# lm7805-power-supply.net
KiCad netlist of a schematic drawn in Altium Designer
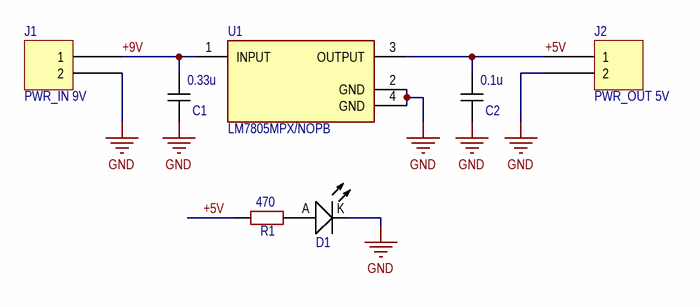
[diagram p0: lm7805-power-supply.SchDoc]

(export (version "E")
  (design (tool "Eeschema 10.0.6"))
  (components
    (comp (ref "C1")
      (value "0.33u")
      (footprint "CAP_CER_1206")
      (description "Cap Cer MLCC SMD 50V 0.33uF X7R 1206 5%")
      (fields
        (field (name "PART NUMBER") "CC1206JRX7R9BB334")
        (field (name "MOUSER PART NUMBER") "603-CC1206JR9BB334")
      )
      (libsource (lib "SssAccesDatbase") (part "Cap"))
    )
    (comp (ref "C2")
      (value "0.1u")
      (footprint "CAP_CER_1206")
      (description "Cap Cer MLCC SMD 50V 0.1uF C0G NP0 1206 5%")
      (fields
        (field (name "PART NUMBER") "C3216C0G1H104J160AA")
        (field (name "MOUSER PART NUMBER") "810-C3216C0G1H104J")
      )
      (libsource (lib "SssAccesDatbase") (part "Cap"))
    )
    (comp (ref "D1")
      (value "Bl 0603")
      (footprint "LED-0603-BLUE")
      (description "LED BLUE DIFFUSED 0603 SMD")
      (fields
        (field (name "PART NUMBER") "150060BS55040")
        (field (name "DIGI-KEY PART NUMBER") "732-12013-1-ND")
      )
      (libsource (lib "SssAccesDatbase") (part "LED_AK"))
    )
    (comp (ref "J1")
      (value "PWR_IN 9V")
      (footprint "TE 282837-2")
      (description "TERM BLK 2P SIDE ENT 5.08MM PCB")
      (fields
        (field (name "PART NUMBER") "282837-2")
        (field (name "MANUFACTURER") "TE Connectivity AMP Connectors")
      )
      (libsource (lib "") (part "2 Pin_1"))
    )
    (comp (ref "J2")
      (value "PWR_OUT 5V")
      (footprint "TE 282837-2")
      (description "TERM BLK 2P SIDE ENT 5.08MM PCB")
      (fields
        (field (name "PART NUMBER") "282837-2")
        (field (name "MANUFACTURER") "TE Connectivity AMP Connectors")
      )
      (libsource (lib "Celestial Altium Library - altium_library") (part "2 Pin"))
    )
    (comp (ref "R1")
      (value "470")
      (footprint "RESC1608(0603)N")
      (description "RES SMD 0603 470  0.5% 25ppm")
      (fields
        (field (name "PART NUMBER") "RN731JTTD4700D25")
        (field (name "MOUSER PART NUMBER") "660-RN731JTTD4700D25")
      )
      (libsource (lib "SssAccesDatbase") (part "Resistor general"))
    )
    (comp (ref "U1")
      (value "LM7805MPX/NOPB")
      (footprint "FP-LM7805MPX-NOPB-MFG")
      (description "IC REG LINEAR 5V 1.5A SOT223-4")
      (fields
        (field (name "MANUFACTURER") "Texas Instruments")
        (field (name "OCTOPART") "https://octopart.com/lm7805mpx%2Fnopb-texas+instruments-74629992")
      )
      (libsource (lib "Altium Content Vault") (part "b4ee7691a89d8e73302b24c49f391f2"))
    )
  )
  (nets
    (net (code "1") (name "/+5V") (class "Default")
      (node (ref "C2") (pin "2") (pinfunction "2_2") (pintype "passive"))
      (node (ref "J2") (pin "1") (pinfunction "1_1") (pintype "passive"))
      (node (ref "R1") (pin "1") (pinfunction "1_1") (pintype "passive"))
      (node (ref "U1") (pin "3") (pinfunction "OUTPUT_3") (pintype "passive"))
    )
    (net (code "2") (name "/+9V") (class "Default")
      (node (ref "C1") (pin "2") (pinfunction "2_2") (pintype "passive"))
      (node (ref "J1") (pin "1") (pinfunction "1_1") (pintype "passive"))
      (node (ref "U1") (pin "1") (pinfunction "INPUT_1") (pintype "power_in"))
    )
    (net (code "3") (name "GND") (class "Default")
      (node (ref "C1") (pin "1") (pinfunction "1_1") (pintype "passive"))
      (node (ref "C2") (pin "1") (pinfunction "1_1") (pintype "passive"))
      (node (ref "D1") (pin "K") (pinfunction "K_K") (pintype "passive"))
      (node (ref "J1") (pin "2") (pinfunction "2_2") (pintype "passive"))
      (node (ref "J2") (pin "2") (pinfunction "2_2") (pintype "passive"))
      (node (ref "U1") (pin "2") (pinfunction "GND_2") (pintype "power_in"))
      (node (ref "U1") (pin "4") (pinfunction "GND_4") (pintype "power_in"))
    )
    (net (code "4") (name "Net-(D1-PadA)") (class "Default")
      (node (ref "D1") (pin "A") (pinfunction "A_A") (pintype "passive"))
      (node (ref "R1") (pin "2") (pinfunction "2_2") (pintype "passive"))
    )
  )
)
